# 1-Schematic_New_Project.net
KiCad netlist of a schematic drawn in EasyEDA
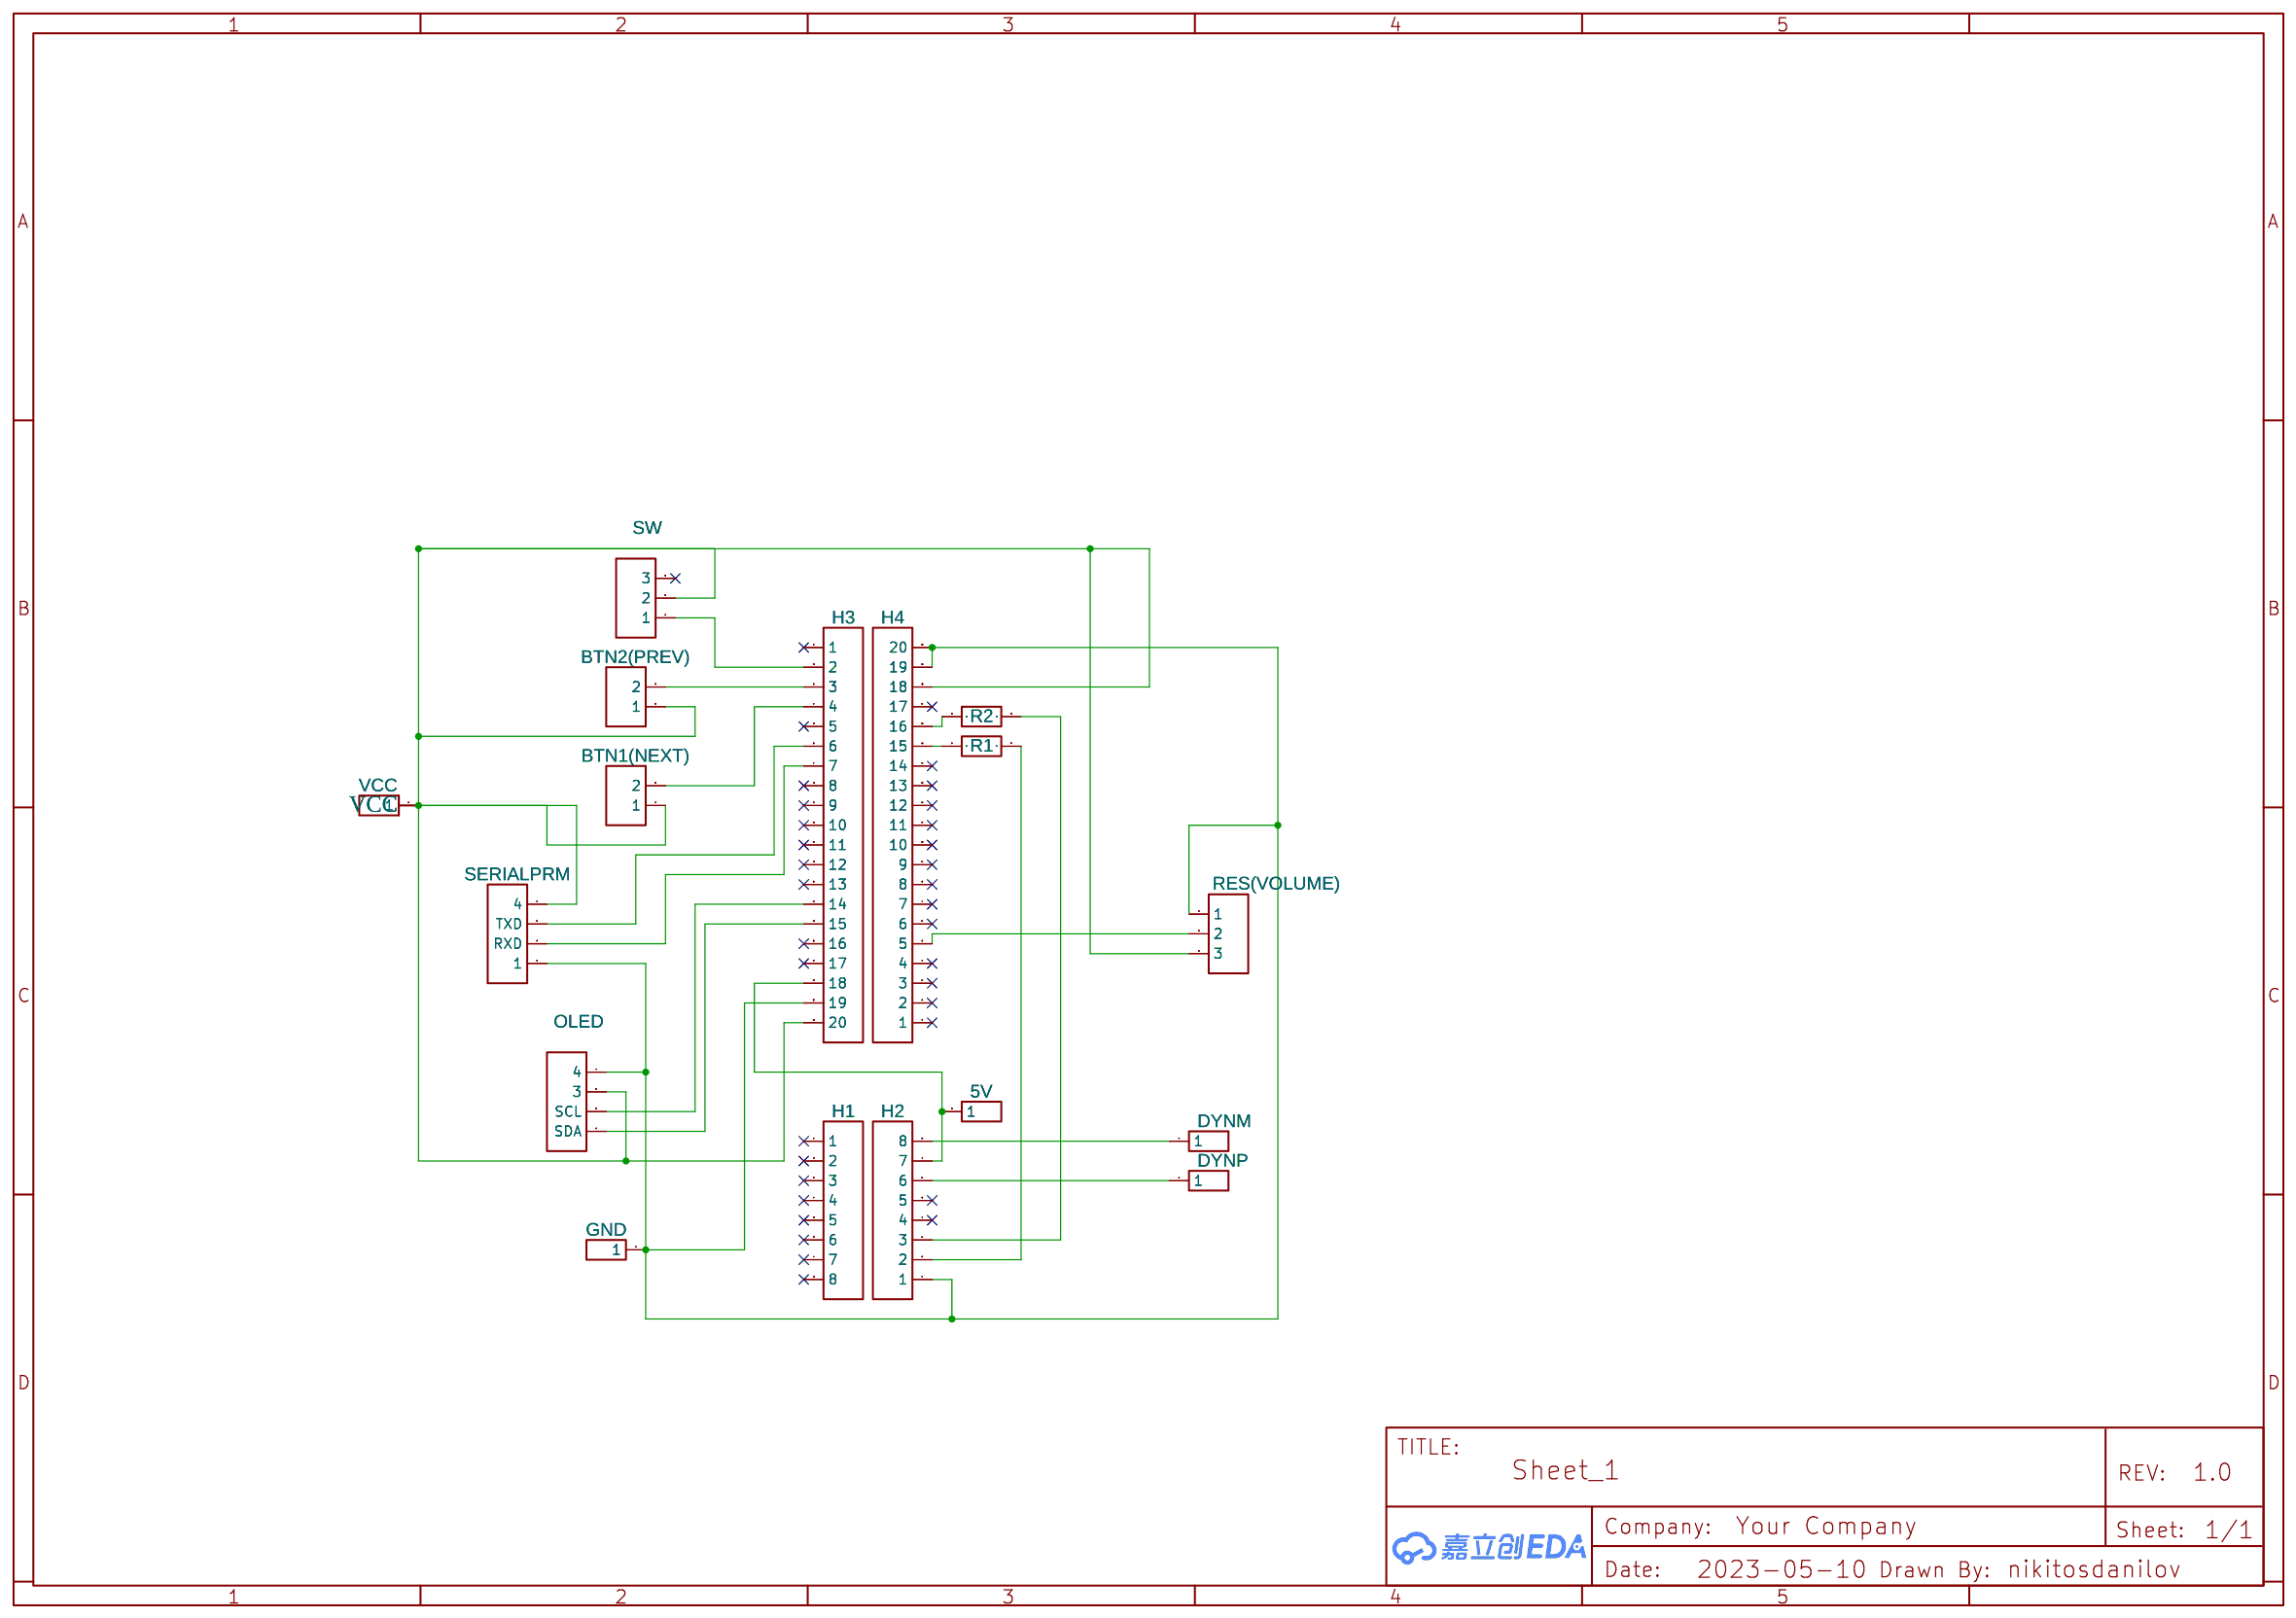
[diagram p0: schematic sheet]

(export (version "E")
  (design (tool "Eeschema 10.0.6"))
  (components
    (comp (ref "5V")
      (value "5V")
      (fields (field (name "BOM_Supplier Part") "C81276"))
      (libsource (lib "") (part "HDR-M-2.54_1x1_1"))
    )
    (comp (ref "BTN1(NEXT)")
      (value "HDR-F-2.54_1x2")
      (fields (field (name "BOM_Supplier Part") "C49661"))
      (libsource (lib "") (part "HDR-F-2.54_1x2_1"))
    )
    (comp (ref "BTN2(PREV)")
      (value "HDR-F-2.54_1x2")
      (fields (field (name "BOM_Supplier Part") "C49661"))
      (libsource (lib "") (part "HDR-F-2.54_1x2"))
    )
    (comp (ref "DYNM")
      (value "5V")
      (fields (field (name "BOM_Supplier Part") "C81276"))
      (libsource (lib "") (part "HDR-M-2.54_1x1_3"))
    )
    (comp (ref "DYNP")
      (value "5V")
      (fields (field (name "BOM_Supplier Part") "C81276"))
      (libsource (lib "") (part "HDR-M-2.54_1x1_2"))
    )
    (comp (ref "GND")
      (value "5V")
      (fields (field (name "BOM_Supplier Part") "C81276"))
      (libsource (lib "") (part "HDR-M-2.54_1x1"))
    )
    (comp (ref "H1")
      (value "HDR-F-2.54_1x8")
      (fields (field (name "BOM_Supplier Part") "C225505"))
      (libsource (lib "") (part "HDR-F-2.54_1x8_1"))
    )
    (comp (ref "H2")
      (value "HDR-F-2.54_1x8")
      (fields (field (name "BOM_Supplier Part") "C225505"))
      (libsource (lib "") (part "HDR-F-2.54_1x8"))
    )
    (comp (ref "H3")
      (value "HDR-F-2.54_1x20")
      (fields (field (name "BOM_Supplier Part") "C50984"))
      (libsource (lib "") (part "HDR-F-2.54_1x20_1"))
    )
    (comp (ref "H4")
      (value "HDR-F-2.54_1x20")
      (fields (field (name "BOM_Supplier Part") "C50984"))
      (libsource (lib "") (part "HDR-F-2.54_1x20"))
    )
    (comp (ref "OLED")
      (value "HDR-F-2.54_1x4")
      (fields (field (name "BOM_Supplier Part") "C225501"))
      (libsource (lib "") (part "HDR-F-2.54_1x4_1"))
    )
    (comp (ref "R1") (value "1k") (libsource (lib "") (part "R_AXIAL-0.4_EU")))
    (comp (ref "R2") (value "1k") (libsource (lib "") (part "R_AXIAL-0.4_EU")))
    (comp (ref "RES(VOLUME)")
      (value "HDR-F-2.54_1x3")
      (fields (field (name "BOM_Supplier Part") "C146690"))
      (libsource (lib "") (part "HDR-F-2.54_1x3_1"))
    )
    (comp (ref "SERIALPRM")
      (value "HDR-F-2.54_1x4")
      (fields (field (name "BOM_Supplier Part") "C225501"))
      (libsource (lib "") (part "HDR-F-2.54_1x4"))
    )
    (comp (ref "SW")
      (value "HDR-F-2.54_1x3")
      (fields (field (name "BOM_Supplier Part") "C146690"))
      (libsource (lib "") (part "HDR-F-2.54_1x3"))
    )
    (comp (ref "VCC")
      (value "5V")
      (fields (field (name "BOM_Supplier Part") "C81276"))
      (libsource (lib "") (part "HDR-M-2.54_1x1_4"))
    )
  )
  (nets
    (net (code "1") (name "Net-(5V-Pad1)") (class "Default")
      (node (ref "5V") (pin "1") (pinfunction "1_1") (pintype "input"))
      (node (ref "H2") (pin "7") (pinfunction "7_7") (pintype "unspecified"))
      (node (ref "H3") (pin "18") (pinfunction "18_18") (pintype "unspecified"))
    )
    (net (code "2") (name "Net-(BTN1(NEXT)-Pad2)") (class "Default")
      (node (ref "BTN1(NEXT)") (pin "2") (pinfunction "2_2") (pintype "input"))
      (node (ref "H3") (pin "4") (pinfunction "4_4") (pintype "unspecified"))
    )
    (net (code "3") (name "Net-(BTN2(PREV)-Pad2)") (class "Default")
      (node (ref "BTN2(PREV)") (pin "2") (pinfunction "2_2") (pintype "input"))
      (node (ref "H3") (pin "3") (pinfunction "3_3") (pintype "unspecified"))
    )
    (net (code "4") (name "Net-(DYNM-Pad1)") (class "Default")
      (node (ref "DYNM") (pin "1") (pinfunction "1_1") (pintype "input"))
      (node (ref "H2") (pin "8") (pinfunction "8_8") (pintype "unspecified"))
    )
    (net (code "5") (name "Net-(DYNP-Pad1)") (class "Default")
      (node (ref "DYNP") (pin "1") (pinfunction "1_1") (pintype "input"))
      (node (ref "H2") (pin "6") (pinfunction "6_6") (pintype "unspecified"))
    )
    (net (code "6") (name "Net-(GND-Pad1)") (class "Default")
      (node (ref "GND") (pin "1") (pinfunction "1_1") (pintype "input"))
      (node (ref "H2") (pin "1") (pinfunction "1_1") (pintype "unspecified"))
      (node (ref "H3") (pin "19") (pinfunction "19_19") (pintype "unspecified"))
      (node (ref "H4") (pin "19") (pinfunction "19_19") (pintype "unspecified"))
      (node (ref "H4") (pin "20") (pinfunction "20_20") (pintype "unspecified"))
      (node (ref "OLED") (pin "4") (pinfunction "4_4") (pintype "unspecified"))
      (node (ref "RES(VOLUME)") (pin "1") (pinfunction "1_1") (pintype "input"))
      (node (ref "SERIALPRM") (pin "1") (pinfunction "1_1") (pintype "unspecified"))
    )
    (net (code "7") (name "Net-(H2-Pad2)") (class "Default")
      (node (ref "H2") (pin "2") (pinfunction "2_2") (pintype "unspecified"))
      (node (ref "R1") (pin "2") (pinfunction "2_2") (pintype "unspecified"))
    )
    (net (code "8") (name "Net-(H2-Pad3)") (class "Default")
      (node (ref "H2") (pin "3") (pinfunction "3_3") (pintype "unspecified"))
      (node (ref "R2") (pin "2") (pinfunction "2_2") (pintype "unspecified"))
    )
    (net (code "9") (name "Net-(H3-Pad2)") (class "Default")
      (node (ref "H3") (pin "2") (pinfunction "2_2") (pintype "unspecified"))
      (node (ref "SW") (pin "1") (pinfunction "1_1") (pintype "input"))
    )
    (net (code "10") (name "Net-(H4-Pad5)") (class "Default")
      (node (ref "H4") (pin "5") (pinfunction "5_5") (pintype "unspecified"))
      (node (ref "RES(VOLUME)") (pin "2") (pinfunction "2_2") (pintype "input"))
    )
    (net (code "11") (name "Net-(H4-Pad15)") (class "Default")
      (node (ref "H4") (pin "15") (pinfunction "15_15") (pintype "unspecified"))
      (node (ref "R1") (pin "1") (pinfunction "1_1") (pintype "unspecified"))
    )
    (net (code "12") (name "Net-(H4-Pad16)") (class "Default")
      (node (ref "H4") (pin "16") (pinfunction "16_16") (pintype "unspecified"))
      (node (ref "R2") (pin "1") (pinfunction "1_1") (pintype "unspecified"))
    )
    (net (code "13") (name "Net-(OLED-SCL)") (class "Default")
      (node (ref "H3") (pin "14") (pinfunction "14_14") (pintype "unspecified"))
      (node (ref "OLED") (pin "2") (pinfunction "SCL_2") (pintype "unspecified"))
    )
    (net (code "14") (name "Net-(OLED-SDA)") (class "Default")
      (node (ref "H3") (pin "15") (pinfunction "15_15") (pintype "unspecified"))
      (node (ref "OLED") (pin "1") (pinfunction "SDA_1") (pintype "unspecified"))
    )
    (net (code "15") (name "Net-(SERIALPRM-RXD)") (class "Default")
      (node (ref "H3") (pin "7") (pinfunction "7_7") (pintype "unspecified"))
      (node (ref "SERIALPRM") (pin "2") (pinfunction "RXD_2") (pintype "unspecified"))
    )
    (net (code "16") (name "Net-(SERIALPRM-TXD)") (class "Default")
      (node (ref "H3") (pin "6") (pinfunction "6_6") (pintype "unspecified"))
      (node (ref "SERIALPRM") (pin "3") (pinfunction "TXD_3") (pintype "unspecified"))
    )
    (net (code "17") (name "VCC") (class "Default")
      (node (ref "BTN1(NEXT)") (pin "1") (pinfunction "1_1") (pintype "input"))
      (node (ref "BTN2(PREV)") (pin "1") (pinfunction "1_1") (pintype "input"))
      (node (ref "H3") (pin "20") (pinfunction "20_20") (pintype "unspecified"))
      (node (ref "H4") (pin "18") (pinfunction "18_18") (pintype "unspecified"))
      (node (ref "OLED") (pin "3") (pinfunction "3_3") (pintype "unspecified"))
      (node (ref "RES(VOLUME)") (pin "3") (pinfunction "3_3") (pintype "input"))
      (node (ref "SERIALPRM") (pin "4") (pinfunction "4_4") (pintype "unspecified"))
      (node (ref "SW") (pin "2") (pinfunction "2_2") (pintype "input"))
      (node (ref "VCC") (pin "1") (pinfunction "1_1") (pintype "input"))
    )
    (net (code "18") (name "unconnected-(H1-Pad1)") (class "Default")
      (node (ref "H1") (pin "1") (pinfunction "1_1") (pintype "unspecified+no_connect"))
    )
    (net (code "19") (name "unconnected-(H1-Pad2)") (class "Default")
      (node (ref "H1") (pin "2") (pinfunction "2_2") (pintype "unspecified+no_connect"))
    )
    (net (code "20") (name "unconnected-(H1-Pad3)") (class "Default")
      (node (ref "H1") (pin "3") (pinfunction "3_3") (pintype "unspecified+no_connect"))
    )
    (net (code "21") (name "unconnected-(H1-Pad4)") (class "Default")
      (node (ref "H1") (pin "4") (pinfunction "4_4") (pintype "unspecified+no_connect"))
    )
    (net (code "22") (name "unconnected-(H1-Pad5)") (class "Default")
      (node (ref "H1") (pin "5") (pinfunction "5_5") (pintype "unspecified+no_connect"))
    )
    (net (code "23") (name "unconnected-(H1-Pad6)") (class "Default")
      (node (ref "H1") (pin "6") (pinfunction "6_6") (pintype "unspecified+no_connect"))
    )
    (net (code "24") (name "unconnected-(H1-Pad7)") (class "Default")
      (node (ref "H1") (pin "7") (pinfunction "7_7") (pintype "unspecified+no_connect"))
    )
    (net (code "25") (name "unconnected-(H1-Pad8)") (class "Default")
      (node (ref "H1") (pin "8") (pinfunction "8_8") (pintype "unspecified+no_connect"))
    )
    (net (code "26") (name "unconnected-(H2-Pad4)") (class "Default")
      (node (ref "H2") (pin "4") (pinfunction "4_4") (pintype "unspecified+no_connect"))
    )
    (net (code "27") (name "unconnected-(H2-Pad5)") (class "Default")
      (node (ref "H2") (pin "5") (pinfunction "5_5") (pintype "unspecified+no_connect"))
    )
    (net (code "28") (name "unconnected-(H3-Pad1)") (class "Default")
      (node (ref "H3") (pin "1") (pinfunction "1_1") (pintype "unspecified+no_connect"))
    )
    (net (code "29") (name "unconnected-(H3-Pad5)") (class "Default")
      (node (ref "H3") (pin "5") (pinfunction "5_5") (pintype "unspecified+no_connect"))
    )
    (net (code "30") (name "unconnected-(H3-Pad8)") (class "Default")
      (node (ref "H3") (pin "8") (pinfunction "8_8") (pintype "unspecified+no_connect"))
    )
    (net (code "31") (name "unconnected-(H3-Pad9)") (class "Default")
      (node (ref "H3") (pin "9") (pinfunction "9_9") (pintype "unspecified+no_connect"))
    )
    (net (code "32") (name "unconnected-(H3-Pad10)") (class "Default")
      (node (ref "H3") (pin "10") (pinfunction "10_10") (pintype "unspecified+no_connect"))
    )
    (net (code "33") (name "unconnected-(H3-Pad11)") (class "Default")
      (node (ref "H3") (pin "11") (pinfunction "11_11") (pintype "unspecified+no_connect"))
    )
    (net (code "34") (name "unconnected-(H3-Pad12)") (class "Default")
      (node (ref "H3") (pin "12") (pinfunction "12_12") (pintype "unspecified+no_connect"))
    )
    (net (code "35") (name "unconnected-(H3-Pad13)") (class "Default")
      (node (ref "H3") (pin "13") (pinfunction "13_13") (pintype "unspecified+no_connect"))
    )
    (net (code "36") (name "unconnected-(H3-Pad16)") (class "Default")
      (node (ref "H3") (pin "16") (pinfunction "16_16") (pintype "unspecified+no_connect"))
    )
    (net (code "37") (name "unconnected-(H3-Pad17)") (class "Default")
      (node (ref "H3") (pin "17") (pinfunction "17_17") (pintype "unspecified+no_connect"))
    )
    (net (code "38") (name "unconnected-(H4-Pad1)") (class "Default")
      (node (ref "H4") (pin "1") (pinfunction "1_1") (pintype "unspecified+no_connect"))
    )
    (net (code "39") (name "unconnected-(H4-Pad2)") (class "Default")
      (node (ref "H4") (pin "2") (pinfunction "2_2") (pintype "unspecified+no_connect"))
    )
    (net (code "40") (name "unconnected-(H4-Pad3)") (class "Default")
      (node (ref "H4") (pin "3") (pinfunction "3_3") (pintype "unspecified+no_connect"))
    )
    (net (code "41") (name "unconnected-(H4-Pad4)") (class "Default")
      (node (ref "H4") (pin "4") (pinfunction "4_4") (pintype "unspecified+no_connect"))
    )
    (net (code "42") (name "unconnected-(H4-Pad6)") (class "Default")
      (node (ref "H4") (pin "6") (pinfunction "6_6") (pintype "unspecified+no_connect"))
    )
    (net (code "43") (name "unconnected-(H4-Pad7)") (class "Default")
      (node (ref "H4") (pin "7") (pinfunction "7_7") (pintype "unspecified+no_connect"))
    )
    (net (code "44") (name "unconnected-(H4-Pad8)") (class "Default")
      (node (ref "H4") (pin "8") (pinfunction "8_8") (pintype "unspecified+no_connect"))
    )
    (net (code "45") (name "unconnected-(H4-Pad9)") (class "Default")
      (node (ref "H4") (pin "9") (pinfunction "9_9") (pintype "unspecified+no_connect"))
    )
    (net (code "46") (name "unconnected-(H4-Pad10)") (class "Default")
      (node (ref "H4") (pin "10") (pinfunction "10_10") (pintype "unspecified+no_connect"))
    )
    (net (code "47") (name "unconnected-(H4-Pad11)") (class "Default")
      (node (ref "H4") (pin "11") (pinfunction "11_11") (pintype "unspecified+no_connect"))
    )
    (net (code "48") (name "unconnected-(H4-Pad12)") (class "Default")
      (node (ref "H4") (pin "12") (pinfunction "12_12") (pintype "unspecified+no_connect"))
    )
    (net (code "49") (name "unconnected-(H4-Pad13)") (class "Default")
      (node (ref "H4") (pin "13") (pinfunction "13_13") (pintype "unspecified+no_connect"))
    )
    (net (code "50") (name "unconnected-(H4-Pad14)") (class "Default")
      (node (ref "H4") (pin "14") (pinfunction "14_14") (pintype "unspecified+no_connect"))
    )
    (net (code "51") (name "unconnected-(H4-Pad17)") (class "Default")
      (node (ref "H4") (pin "17") (pinfunction "17_17") (pintype "unspecified+no_connect"))
    )
    (net (code "52") (name "unconnected-(SW-Pad3)") (class "Default")
      (node (ref "SW") (pin "3") (pinfunction "3_3") (pintype "input+no_connect"))
    )
  )
)
